# SCH_Sensor_Board_2021-11-23.net
KiCad netlist of a schematic drawn in EasyEDA
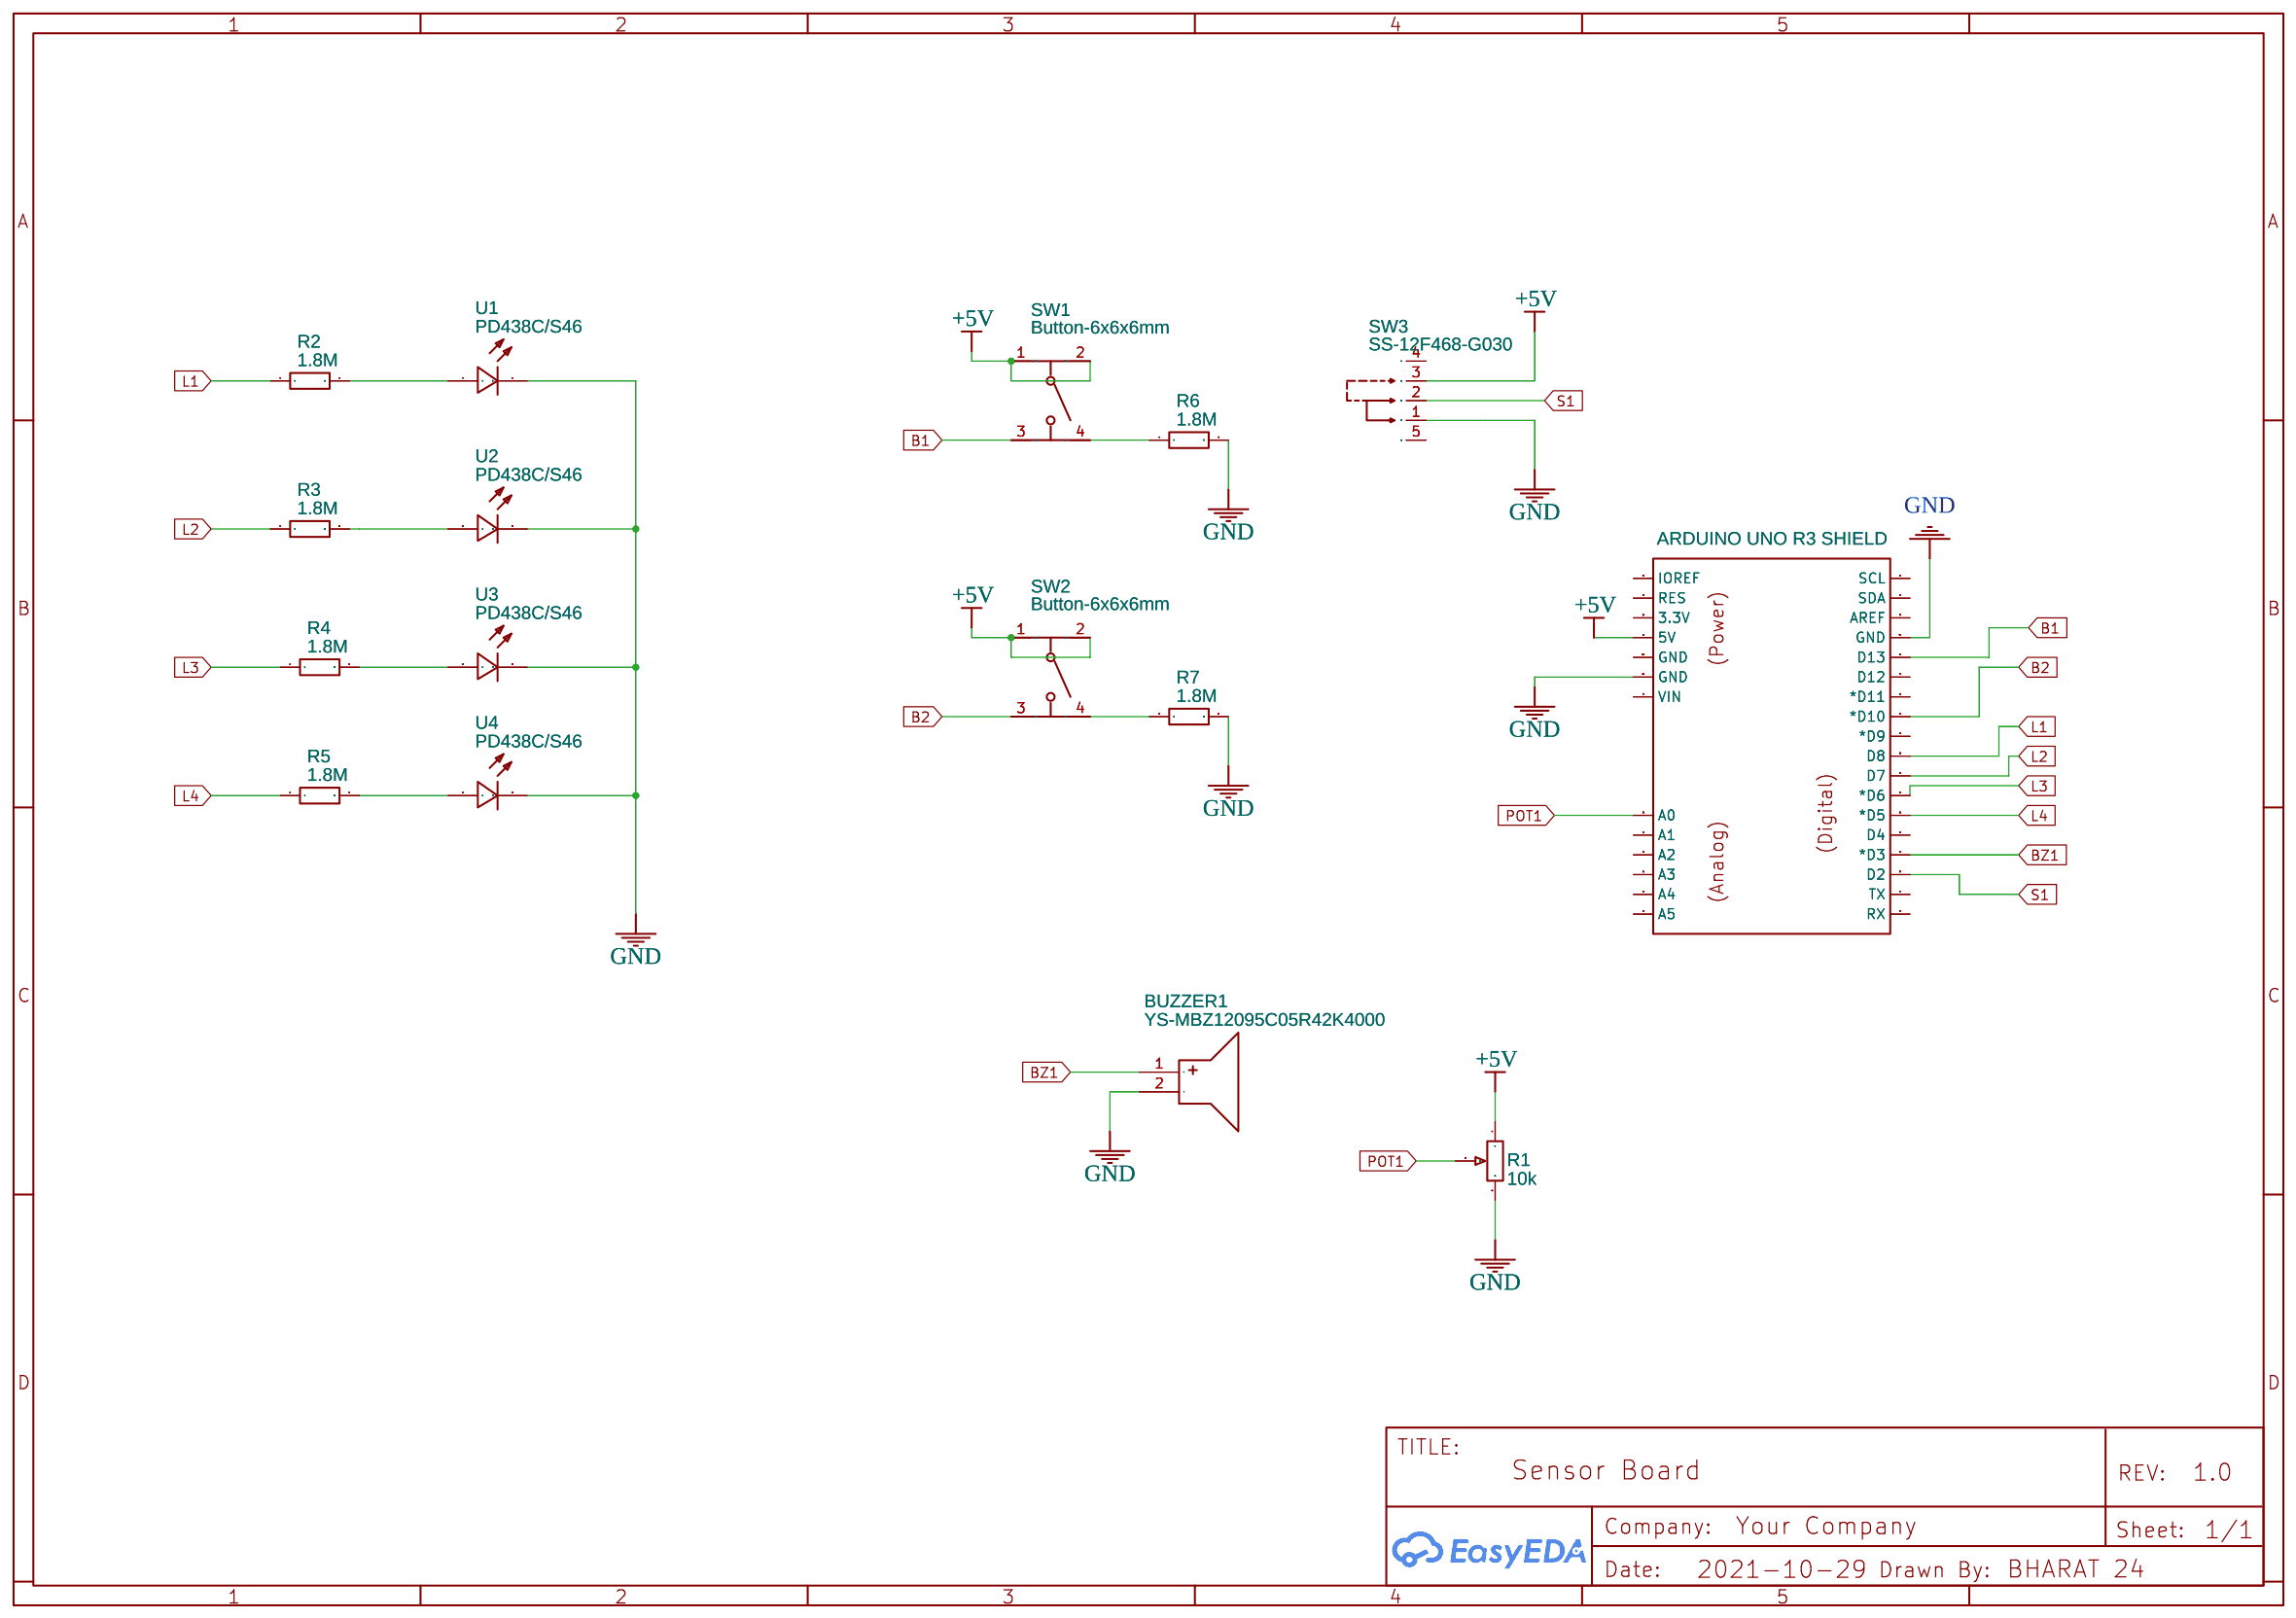
[diagram p0: schematic sheet]

(export (version "E")
  (design (tool "Eeschema 10.0.6"))
  (components
    (comp (ref "B1")
      (value "ARDUINO UNO R3 SHIELD")
      (fields (field (name "Manufacturer") "?"))
      (libsource (lib "") (part "ARDUINO UNO R3 SHIELD"))
    )
    (comp (ref "BUZZER1")
      (value "YS-MBZ12095C05R42K4000")
      (fields (field (name "BOM_Supplier Part") "C2891357"))
      (libsource (lib "") (part "YS-MBZ12095C05R42K4000"))
    )
    (comp (ref "R1")
      (value "10k")
      (fields
        (field (name "BOM_Manufacturer Part") "3362F-1-103LF")
        (field (name "BOM_Supplier Part") "3362F-1-103LF-ND")
      )
      (libsource (lib "") (part "3362F-1-103LF"))
    )
    (comp (ref "R2")
      (value "1.8M")
      (fields
        (field (name "BOM_Manufacturer Part") "0603WAF1804T5E")
        (field (name "BOM_Supplier Part") "C13318")
      )
      (libsource (lib "") (part "0603WAF1804T5E"))
    )
    (comp (ref "R3")
      (value "1.8M")
      (fields
        (field (name "BOM_Manufacturer Part") "0603WAF1804T5E")
        (field (name "BOM_Supplier Part") "C13318")
      )
      (libsource (lib "") (part "0603WAF1804T5E"))
    )
    (comp (ref "R4")
      (value "1.8M")
      (fields
        (field (name "BOM_Manufacturer Part") "0603WAF1804T5E")
        (field (name "BOM_Supplier Part") "C13318")
      )
      (libsource (lib "") (part "0603WAF1804T5E"))
    )
    (comp (ref "R5")
      (value "1.8M")
      (fields
        (field (name "BOM_Manufacturer Part") "0603WAF1804T5E")
        (field (name "BOM_Supplier Part") "C13318")
      )
      (libsource (lib "") (part "0603WAF1804T5E"))
    )
    (comp (ref "R6")
      (value "1.8M")
      (fields
        (field (name "BOM_Manufacturer Part") "0603WAF1804T5E")
        (field (name "BOM_Supplier Part") "C13318")
      )
      (libsource (lib "") (part "0603WAF1804T5E"))
    )
    (comp (ref "R7")
      (value "1.8M")
      (fields
        (field (name "BOM_Manufacturer Part") "0603WAF1804T5E")
        (field (name "BOM_Supplier Part") "C13318")
      )
      (libsource (lib "") (part "0603WAF1804T5E"))
    )
    (comp (ref "SW1")
      (value "Button-6x6x6mm")
      (fields
        (field (name "BOM_Manufacturer Part") "Switch,6*6*6Plastic head,260G, 0.25mm,Straight line")
        (field (name "BOM_Supplier Part") "C71836")
      )
      (libsource (lib "") (part "Button-6x6x6mm"))
    )
    (comp (ref "SW2")
      (value "Button-6x6x6mm")
      (fields
        (field (name "BOM_Manufacturer Part") "Switch,6*6*6Plastic head,260G, 0.25mm,Straight line")
        (field (name "BOM_Supplier Part") "C71836")
      )
      (libsource (lib "") (part "Button-6x6x6mm"))
    )
    (comp (ref "SW3")
      (value "SS-12F468-G030")
      (fields (field (name "BOM_Supplier Part") "C2848904"))
      (libsource (lib "") (part "SS-12F468-G030"))
    )
    (comp (ref "U1")
      (value "PD438C/S46")
      (fields (field (name "BOM_Supplier Part") "C146238"))
      (libsource (lib "") (part "PD438C/S46"))
    )
    (comp (ref "U2")
      (value "PD438C/S46")
      (fields (field (name "BOM_Supplier Part") "C146238"))
      (libsource (lib "") (part "PD438C/S46"))
    )
    (comp (ref "U3")
      (value "PD438C/S46")
      (fields (field (name "BOM_Supplier Part") "C146238"))
      (libsource (lib "") (part "PD438C/S46"))
    )
    (comp (ref "U4")
      (value "PD438C/S46")
      (fields (field (name "BOM_Supplier Part") "C146238"))
      (libsource (lib "") (part "PD438C/S46"))
    )
  )
  (nets
    (net (code "1") (name "+5V") (class "Default")
      (node (ref "B1") (pin "5V") (pinfunction "5V_5V") (pintype "unspecified"))
      (node (ref "R1") (pin "1") (pinfunction "1_1") (pintype "input"))
      (node (ref "SW1") (pin "1") (pinfunction "1_1") (pintype "unspecified"))
      (node (ref "SW1") (pin "2") (pinfunction "2_2") (pintype "unspecified"))
      (node (ref "SW2") (pin "1") (pinfunction "1_1") (pintype "unspecified"))
      (node (ref "SW2") (pin "2") (pinfunction "2_2") (pintype "unspecified"))
      (node (ref "SW3") (pin "3") (pinfunction "3_3") (pintype "unspecified"))
    )
    (net (code "2") (name "B1") (class "Default")
      (node (ref "B1") (pin "D13") (pinfunction "D13_D13") (pintype "unspecified"))
      (node (ref "SW1") (pin "3") (pinfunction "3_3") (pintype "unspecified"))
    )
    (net (code "3") (name "B2") (class "Default")
      (node (ref "B1") (pin "D10") (pinfunction "*D10_D10") (pintype "unspecified"))
      (node (ref "SW2") (pin "3") (pinfunction "3_3") (pintype "unspecified"))
    )
    (net (code "4") (name "BZ1") (class "Default")
      (node (ref "B1") (pin "D3") (pinfunction "*D3_D3") (pintype "unspecified"))
      (node (ref "BUZZER1") (pin "1") (pinfunction "+_1") (pintype "unspecified"))
    )
    (net (code "5") (name "GND") (class "Default")
      (node (ref "B1") (pin "GND@0") (pinfunction "GND_GND@0") (pintype "unspecified"))
      (node (ref "B1") (pin "GND@1") (pinfunction "GND_GND@1") (pintype "unspecified"))
      (node (ref "BUZZER1") (pin "2") (pinfunction "-_2") (pintype "unspecified"))
      (node (ref "R1") (pin "3") (pinfunction "3_3") (pintype "input"))
      (node (ref "R6") (pin "2") (pinfunction "2_2") (pintype "input"))
      (node (ref "R7") (pin "2") (pinfunction "2_2") (pintype "input"))
      (node (ref "SW3") (pin "1") (pinfunction "1_1") (pintype "unspecified"))
      (node (ref "U1") (pin "2") (pinfunction "C_2") (pintype "unspecified"))
      (node (ref "U2") (pin "2") (pinfunction "C_2") (pintype "unspecified"))
      (node (ref "U3") (pin "2") (pinfunction "C_2") (pintype "unspecified"))
      (node (ref "U4") (pin "2") (pinfunction "C_2") (pintype "unspecified"))
    )
    (net (code "6") (name "L1") (class "Default")
      (node (ref "B1") (pin "D8") (pinfunction "D8_D8") (pintype "unspecified"))
      (node (ref "R2") (pin "1") (pinfunction "1_1") (pintype "input"))
    )
    (net (code "7") (name "L2") (class "Default")
      (node (ref "B1") (pin "D7") (pinfunction "D7_D7") (pintype "unspecified"))
      (node (ref "R3") (pin "1") (pinfunction "1_1") (pintype "input"))
    )
    (net (code "8") (name "L3") (class "Default")
      (node (ref "B1") (pin "D6") (pinfunction "*D6_D6") (pintype "unspecified"))
      (node (ref "R4") (pin "1") (pinfunction "1_1") (pintype "input"))
    )
    (net (code "9") (name "L4") (class "Default")
      (node (ref "B1") (pin "D5") (pinfunction "*D5_D5") (pintype "unspecified"))
      (node (ref "R5") (pin "1") (pinfunction "1_1") (pintype "input"))
    )
    (net (code "10") (name "Net-(R6-Pad1)") (class "Default")
      (node (ref "R6") (pin "1") (pinfunction "1_1") (pintype "input"))
      (node (ref "SW1") (pin "4") (pinfunction "4_4") (pintype "unspecified"))
    )
    (net (code "11") (name "Net-(R7-Pad1)") (class "Default")
      (node (ref "R7") (pin "1") (pinfunction "1_1") (pintype "input"))
      (node (ref "SW2") (pin "4") (pinfunction "4_4") (pintype "unspecified"))
    )
    (net (code "12") (name "Net-(U1-A)") (class "Default")
      (node (ref "R2") (pin "2") (pinfunction "2_2") (pintype "input"))
      (node (ref "U1") (pin "1") (pinfunction "A_1") (pintype "unspecified"))
    )
    (net (code "13") (name "Net-(U2-A)") (class "Default")
      (node (ref "R3") (pin "2") (pinfunction "2_2") (pintype "input"))
      (node (ref "U2") (pin "1") (pinfunction "A_1") (pintype "unspecified"))
    )
    (net (code "14") (name "Net-(U3-A)") (class "Default")
      (node (ref "R4") (pin "2") (pinfunction "2_2") (pintype "input"))
      (node (ref "U3") (pin "1") (pinfunction "A_1") (pintype "unspecified"))
    )
    (net (code "15") (name "Net-(U4-A)") (class "Default")
      (node (ref "R5") (pin "2") (pinfunction "2_2") (pintype "input"))
      (node (ref "U4") (pin "1") (pinfunction "A_1") (pintype "unspecified"))
    )
    (net (code "16") (name "POT1") (class "Default")
      (node (ref "B1") (pin "A0") (pinfunction "A0_A0") (pintype "unspecified"))
      (node (ref "R1") (pin "2") (pinfunction "2_2") (pintype "input"))
    )
    (net (code "17") (name "S1") (class "Default")
      (node (ref "B1") (pin "D2") (pinfunction "D2_D2") (pintype "unspecified"))
      (node (ref "SW3") (pin "2") (pinfunction "2_2") (pintype "unspecified"))
    )
    (net (code "18") (name "unconnected-(B1-*D9-PadD9)") (class "Default")
      (node (ref "B1") (pin "D9") (pinfunction "*D9_D9") (pintype "unspecified"))
    )
    (net (code "19") (name "unconnected-(B1-*D11-PadD11)") (class "Default")
      (node (ref "B1") (pin "D11") (pinfunction "*D11_D11") (pintype "unspecified"))
    )
    (net (code "20") (name "unconnected-(B1-GND-PadGND@2)") (class "Default")
      (node (ref "B1") (pin "GND@2") (pinfunction "GND_GND@2") (pintype "unspecified"))
    )
    (net (code "21") (name "unconnected-(B1-Pad3.3V)") (class "Default")
      (node (ref "B1") (pin "3.3V") (pinfunction "3.3V_3.3V") (pintype "unspecified"))
    )
    (net (code "22") (name "unconnected-(B1-PadA1)") (class "Default")
      (node (ref "B1") (pin "A1") (pinfunction "A1_A1") (pintype "unspecified"))
    )
    (net (code "23") (name "unconnected-(B1-PadA2)") (class "Default")
      (node (ref "B1") (pin "A2") (pinfunction "A2_A2") (pintype "unspecified"))
    )
    (net (code "24") (name "unconnected-(B1-PadA3)") (class "Default")
      (node (ref "B1") (pin "A3") (pinfunction "A3_A3") (pintype "unspecified"))
    )
    (net (code "25") (name "unconnected-(B1-PadA4)") (class "Default")
      (node (ref "B1") (pin "A4") (pinfunction "A4_A4") (pintype "unspecified"))
    )
    (net (code "26") (name "unconnected-(B1-PadA5)") (class "Default")
      (node (ref "B1") (pin "A5") (pinfunction "A5_A5") (pintype "unspecified"))
    )
    (net (code "27") (name "unconnected-(B1-PadAREF)") (class "Default")
      (node (ref "B1") (pin "AREF") (pinfunction "AREF_AREF") (pintype "unspecified"))
    )
    (net (code "28") (name "unconnected-(B1-PadD4)") (class "Default")
      (node (ref "B1") (pin "D4") (pinfunction "D4_D4") (pintype "unspecified"))
    )
    (net (code "29") (name "unconnected-(B1-PadD12)") (class "Default")
      (node (ref "B1") (pin "D12") (pinfunction "D12_D12") (pintype "unspecified"))
    )
    (net (code "30") (name "unconnected-(B1-PadIOREF)") (class "Default")
      (node (ref "B1") (pin "IOREF") (pinfunction "IOREF_IOREF") (pintype "unspecified"))
    )
    (net (code "31") (name "unconnected-(B1-PadRES)") (class "Default")
      (node (ref "B1") (pin "RES") (pinfunction "RES_RES") (pintype "unspecified"))
    )
    (net (code "32") (name "unconnected-(B1-PadRX)") (class "Default")
      (node (ref "B1") (pin "RX") (pinfunction "RX_RX") (pintype "unspecified"))
    )
    (net (code "33") (name "unconnected-(B1-PadSCL)") (class "Default")
      (node (ref "B1") (pin "SCL") (pinfunction "SCL_SCL") (pintype "unspecified"))
    )
    (net (code "34") (name "unconnected-(B1-PadSDA)") (class "Default")
      (node (ref "B1") (pin "SDA") (pinfunction "SDA_SDA") (pintype "unspecified"))
    )
    (net (code "35") (name "unconnected-(B1-PadTX)") (class "Default")
      (node (ref "B1") (pin "TX") (pinfunction "TX_TX") (pintype "unspecified"))
    )
    (net (code "36") (name "unconnected-(B1-PadVIN)") (class "Default")
      (node (ref "B1") (pin "VIN") (pinfunction "VIN_VIN") (pintype "unspecified"))
    )
    (net (code "37") (name "unconnected-(SW3-Pad4)") (class "Default")
      (node (ref "SW3") (pin "4") (pinfunction "4_4") (pintype "unspecified"))
    )
    (net (code "38") (name "unconnected-(SW3-Pad5)") (class "Default")
      (node (ref "SW3") (pin "5") (pinfunction "5_5") (pintype "unspecified"))
    )
  )
)
